# schematics.net
KiCad netlist of a schematic drawn in EAGLE
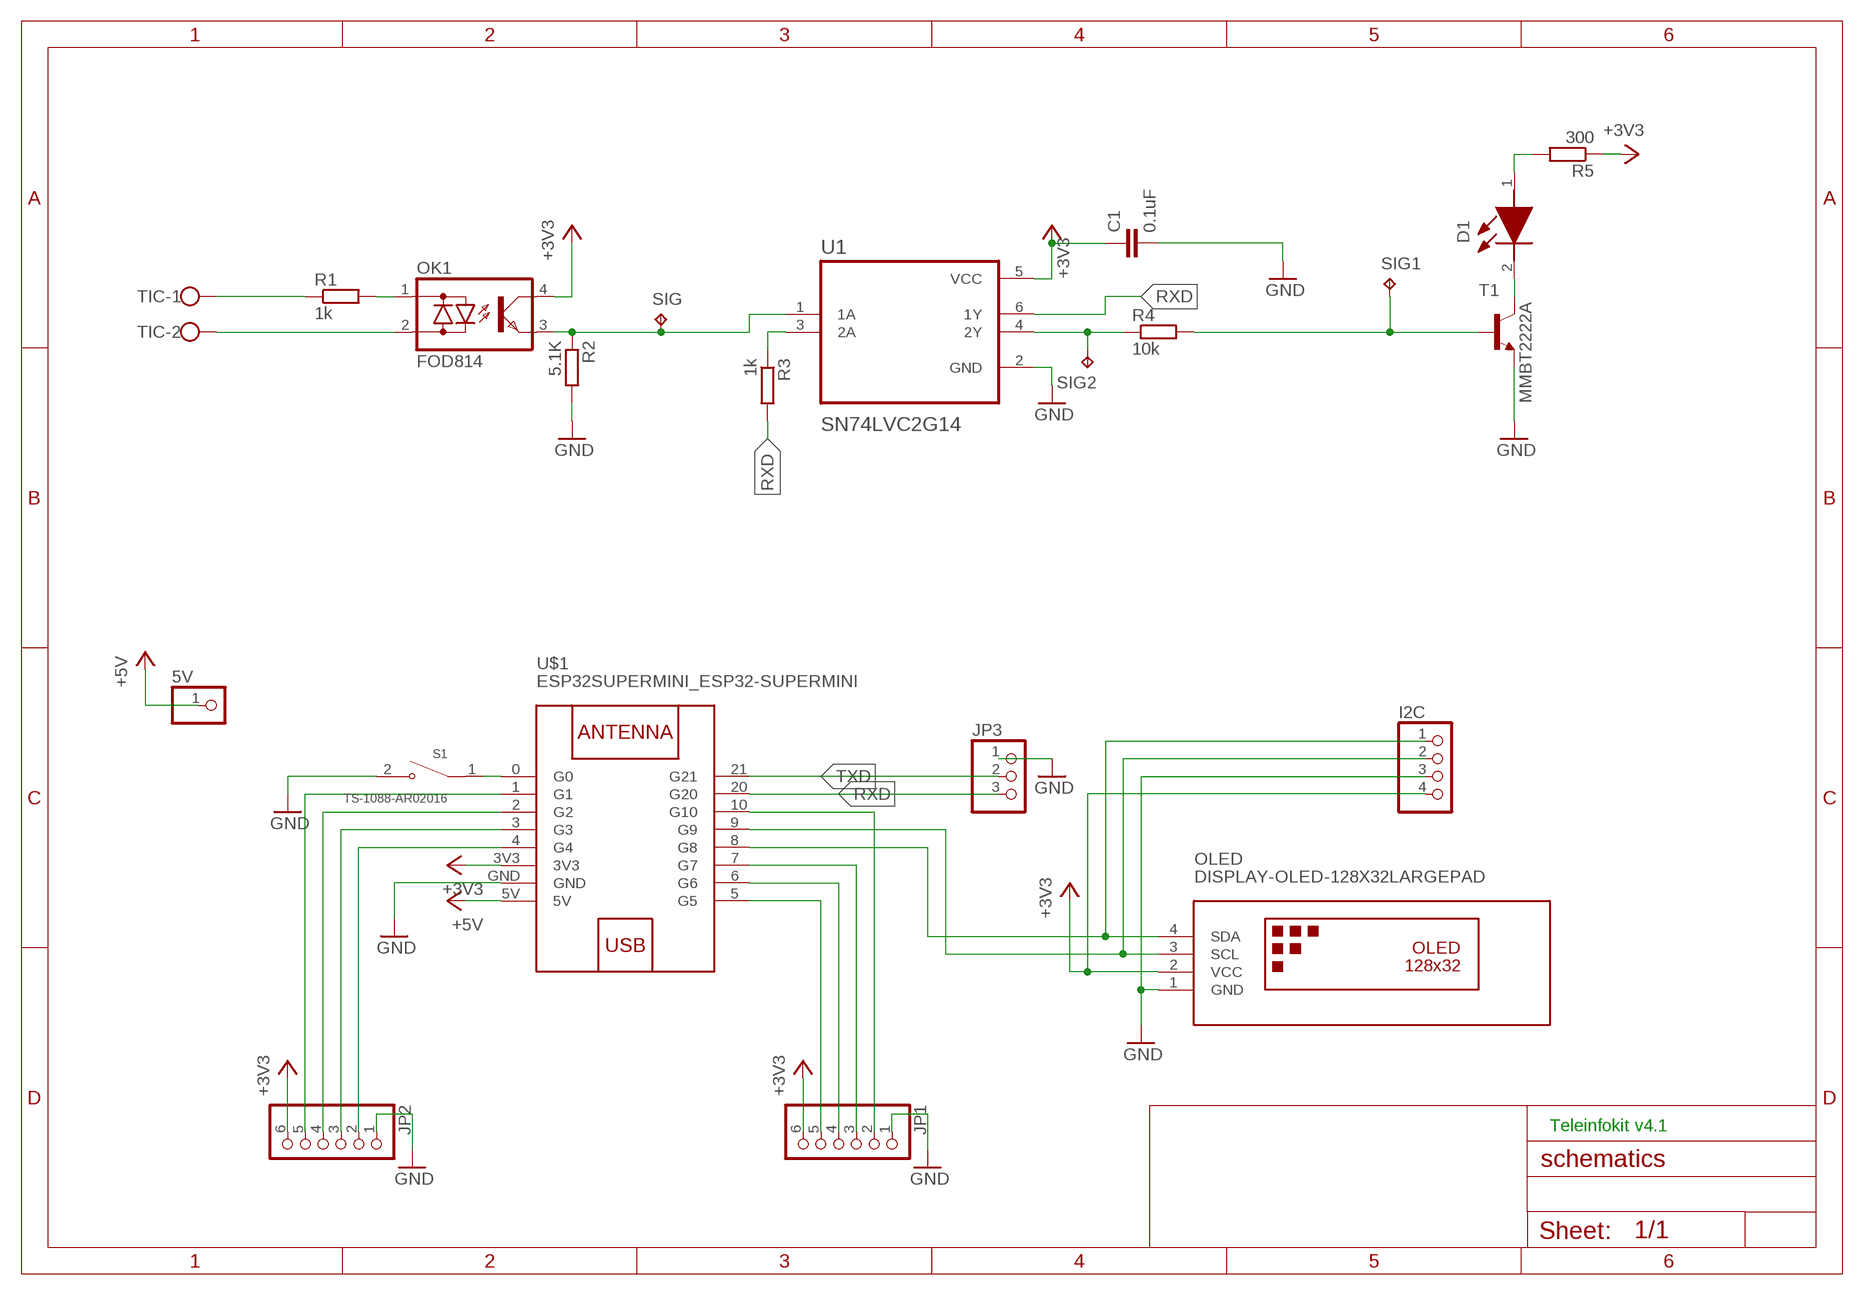
[diagram p0: schematic, sheet 1]

(export (version "E")
  (design (tool "Eeschema 10.0.6"))
  (components
    (comp (ref "5V")
      (value "PINHD-1X1")
      (footprint "eagle-import:1X01")
      (libsource (lib "eagle-import") (part "PINHD-1X1"))
    )
    (comp (ref "C1")
      (value "0.1uF")
      (footprint "eagle-import:C0402K")
      (fields (field (name "LCSC_PART") "C1525"))
      (libsource (lib "eagle-import") (part "C-EUC0402K"))
    )
    (comp (ref "D1")
      (value "17-21SURC_S530-A2_TR8")
      (footprint "eagle-import:1721SURCS530A2TR8")
      (fields (field (name "ARROW_PART_NUMBER") "17-21SURC/S530-A2/TR8"))
      (libsource (lib "eagle-import") (part "17-21SURC_S530-A2_TR8"))
    )
    (comp (ref "I2C")
      (value "PINHD-1X4ROUNDLARGE")
      (footprint "eagle-import:1X04ROUNDLARGE")
      (libsource (lib "eagle-import") (part "PINHD-1X4ROUNDLARGE"))
    )
    (comp (ref "JP1")
      (value "PINHD-1X6CB")
      (footprint "eagle-import:1X06-CLEANBIG")
      (libsource (lib "eagle-import") (part "PINHD-1X6CB"))
    )
    (comp (ref "JP2")
      (value "PINHD-1X6CB")
      (footprint "eagle-import:1X06-CLEANBIG")
      (libsource (lib "eagle-import") (part "PINHD-1X6CB"))
    )
    (comp (ref "JP3")
      (value "PINHD-1X3")
      (footprint "eagle-import:1X03")
      (libsource (lib "eagle-import") (part "PINHD-1X3"))
    )
    (comp (ref "OK1")
      (value "FOD814")
      (footprint "eagle-import:DIL4-SMD")
      (fields
        (field (name "MF") "VISHAY/TELEFUNKEN")
        (field (name "MPN") "SFH6206-3")
        (field (name "LCSC_PART") "C479718")
      )
      (libsource (lib "eagle-import") (part "SFH6206"))
    )
    (comp (ref "OLED")
      (value "DISPLAY-OLED-128X32LARGEPAD")
      (footprint "eagle-import:DISPLAY-OLED-128X32LARGE")
      (fields (field (name "LCSC_PART") "C2718488"))
      (libsource (lib "eagle-import") (part "DISPLAY-OLED-128X32LARGEPAD"))
    )
    (comp (ref "R1")
      (value "1k")
      (footprint "eagle-import:R0805")
      (fields (field (name "LCSC_PART") "C17513"))
      (libsource (lib "eagle-import") (part "R-EU_R0805"))
    )
    (comp (ref "R2")
      (value "5.1K")
      (footprint "eagle-import:R0603")
      (fields (field (name "LCSC_PART") "C23186"))
      (libsource (lib "eagle-import") (part "R-EU_R0603"))
    )
    (comp (ref "R3")
      (value "1k")
      (footprint "eagle-import:R0805")
      (fields (field (name "LCSC_PART") "C17414"))
      (libsource (lib "eagle-import") (part "R-EU_R0805"))
    )
    (comp (ref "R4")
      (value "10k")
      (footprint "eagle-import:R0805")
      (fields (field (name "LCSC_PART") "C17414"))
      (libsource (lib "eagle-import") (part "R-EU_R0805"))
    )
    (comp (ref "R5")
      (value "300")
      (footprint "eagle-import:R0805")
      (fields (field (name "LCSC_PART") "C17617"))
      (libsource (lib "eagle-import") (part "R-EU_R0805"))
    )
    (comp (ref "S1")
      (value "TS-1088-AR02016")
      (footprint "eagle-import:SW_TS-1088-AR02016")
      (fields (field (name "MF") "Xunpu") (field (name "LCSC_PART") "C720477"))
      (libsource (lib "eagle-import") (part "TS-1088-AR02016"))
    )
    (comp (ref "SIG")
      (value "TPB1,27")
      (footprint "eagle-import:B1,27")
      (libsource (lib "eagle-import") (part "TPB1,27"))
    )
    (comp (ref "SIG1")
      (value "TPB1,27")
      (footprint "eagle-import:B1,27")
      (libsource (lib "eagle-import") (part "TPB1,27"))
    )
    (comp (ref "SIG2")
      (value "TPB1,27")
      (footprint "eagle-import:B1,27")
      (libsource (lib "eagle-import") (part "TPB1,27"))
    )
    (comp (ref "T1")
      (value "MMBT2222A")
      (footprint "eagle-import:SOT23-BEC")
      (fields (field (name "LCSC_PART") "C8512"))
      (libsource (lib "eagle-import") (part "-NPN-SOT23-BECMMBT2222ALT1"))
    )
    (comp (ref "TIC")
      (value "W237-102")
      (footprint "eagle-import:W237-102")
      (fields (field (name "MPN") "237-102"))
      (libsource (lib "eagle-import") (part "W237-102"))
    )
    (comp (ref "U$1")
      (value "ESP32SUPERMINI_ESP32-SUPERMINI")
      (footprint "eagle-import:ESP32SUPERMINI_ESP32-SUPERMINI")
      (libsource (lib "eagle-import") (part "ESP32SUPERMINI_ESP32-SUPERMINI"))
    )
    (comp (ref "U1")
      (value "SN74LVC2G14")
      (footprint "eagle-import:SOT95P280X145-6N")
      (fields
        (field (name "MF") "Texas Instruments")
        (field (name "MP") "SN74LVC2G14DBVR")
        (field (name "LCSC_PART") "C12401")
      )
      (libsource (lib "eagle-import") (part "SN74LVC2G14DBVR"))
    )
  )
  (nets
    (net (code "1") (name "+3V3") (class "Default")
      (node (ref "C1") (pin "1") (pinfunction "1_1") (pintype "passive"))
      (node (ref "I2C") (pin "4") (pinfunction "4_4") (pintype "passive"))
      (node (ref "JP1") (pin "6") (pinfunction "6_6") (pintype "passive"))
      (node (ref "JP2") (pin "6") (pinfunction "6_6") (pintype "passive"))
      (node (ref "OK1") (pin "4") (pinfunction "C_4") (pintype "passive"))
      (node (ref "OLED") (pin "2") (pinfunction "VCC_2") (pintype "power_in"))
      (node (ref "R5") (pin "1") (pinfunction "1_1") (pintype "passive"))
      (node (ref "U$1") (pin "3V3") (pinfunction "3V3_3V3") (pintype "power_in"))
      (node (ref "U1") (pin "5") (pinfunction "VCC_5") (pintype "power_in"))
    )
    (net (code "2") (name "+5V") (class "Default")
      (node (ref "5V") (pin "1") (pinfunction "1_1") (pintype "passive"))
      (node (ref "U$1") (pin "5V") (pinfunction "5V_5V") (pintype "power_in"))
    )
    (net (code "3") (name "GND") (class "Default")
      (node (ref "C1") (pin "2") (pinfunction "2_2") (pintype "passive"))
      (node (ref "I2C") (pin "3") (pinfunction "3_3") (pintype "passive"))
      (node (ref "JP1") (pin "1") (pinfunction "1_1") (pintype "passive"))
      (node (ref "JP2") (pin "1") (pinfunction "1_1") (pintype "passive"))
      (node (ref "JP3") (pin "1") (pinfunction "1_1") (pintype "passive"))
      (node (ref "OLED") (pin "1") (pinfunction "GND_1") (pintype "power_in"))
      (node (ref "R2") (pin "2") (pinfunction "2_2") (pintype "passive"))
      (node (ref "S1") (pin "2") (pinfunction "2_2") (pintype "passive"))
      (node (ref "T1") (pin "E") (pinfunction "E_E") (pintype "passive"))
      (node (ref "U$1") (pin "GND") (pinfunction "GND_GND") (pintype "power_in"))
      (node (ref "U1") (pin "2") (pinfunction "GND_2") (pintype "power_in"))
    )
    (net (code "4") (name "Net-(D1-A)") (class "Default")
      (node (ref "D1") (pin "1") (pinfunction "A_1") (pintype "bidirectional"))
      (node (ref "R5") (pin "2") (pinfunction "2_2") (pintype "passive"))
    )
    (net (code "5") (name "Net-(D1-K)") (class "Default")
      (node (ref "D1") (pin "2") (pinfunction "K_2") (pintype "bidirectional"))
      (node (ref "T1") (pin "C") (pinfunction "C_C") (pintype "passive"))
    )
    (net (code "6") (name "Net-(OK1-AC1)") (class "Default")
      (node (ref "OK1") (pin "1") (pinfunction "AC1_1") (pintype "passive"))
      (node (ref "R1") (pin "2") (pinfunction "2_2") (pintype "passive"))
    )
    (net (code "7") (name "Net-(OK1-AC2)") (class "Default")
      (node (ref "OK1") (pin "2") (pinfunction "AC2_2") (pintype "passive"))
      (node (ref "TIC") (pin "2") (pinfunction "KL_2") (pintype "passive"))
    )
    (net (code "8") (name "Net-(OK1-E)") (class "Default")
      (node (ref "OK1") (pin "3") (pinfunction "E_3") (pintype "passive"))
      (node (ref "R2") (pin "1") (pinfunction "1_1") (pintype "passive"))
      (node (ref "SIG") (pin "TP") (pinfunction "TP_TP") (pintype "input"))
      (node (ref "U1") (pin "1") (pinfunction "1A_1") (pintype "input"))
    )
    (net (code "9") (name "Net-(OLED-SCL)") (class "Default")
      (node (ref "I2C") (pin "2") (pinfunction "2_2") (pintype "passive"))
      (node (ref "OLED") (pin "3") (pinfunction "SCL_3") (pintype "bidirectional"))
      (node (ref "U$1") (pin "9") (pinfunction "G9_9") (pintype "bidirectional"))
    )
    (net (code "10") (name "Net-(OLED-SDA)") (class "Default")
      (node (ref "I2C") (pin "1") (pinfunction "1_1") (pintype "passive"))
      (node (ref "OLED") (pin "4") (pinfunction "SDA_4") (pintype "bidirectional"))
      (node (ref "U$1") (pin "8") (pinfunction "G8_8") (pintype "bidirectional"))
    )
    (net (code "11") (name "Net-(R4-Pad2)") (class "Default")
      (node (ref "R4") (pin "2") (pinfunction "2_2") (pintype "passive"))
      (node (ref "SIG1") (pin "TP") (pinfunction "TP_TP") (pintype "input"))
      (node (ref "T1") (pin "B") (pinfunction "B_B") (pintype "passive"))
    )
    (net (code "12") (name "Net-(TICA-KL)") (class "Default")
      (node (ref "R1") (pin "1") (pinfunction "1_1") (pintype "passive"))
      (node (ref "TIC") (pin "1") (pinfunction "KL_1") (pintype "passive"))
    )
    (net (code "13") (name "Net-(U$1-G0)") (class "Default")
      (node (ref "S1") (pin "1") (pinfunction "1_1") (pintype "passive"))
      (node (ref "U$1") (pin "0") (pinfunction "G0_0") (pintype "bidirectional"))
    )
    (net (code "14") (name "Net-(U$1-G1)") (class "Default")
      (node (ref "JP2") (pin "5") (pinfunction "5_5") (pintype "passive"))
      (node (ref "U$1") (pin "1") (pinfunction "G1_1") (pintype "bidirectional"))
    )
    (net (code "15") (name "Net-(U$1-G2)") (class "Default")
      (node (ref "JP2") (pin "4") (pinfunction "4_4") (pintype "passive"))
      (node (ref "U$1") (pin "2") (pinfunction "G2_2") (pintype "bidirectional"))
    )
    (net (code "16") (name "Net-(U$1-G3)") (class "Default")
      (node (ref "JP2") (pin "3") (pinfunction "3_3") (pintype "passive"))
      (node (ref "U$1") (pin "3") (pinfunction "G3_3") (pintype "bidirectional"))
    )
    (net (code "17") (name "Net-(U$1-G4)") (class "Default")
      (node (ref "JP2") (pin "2") (pinfunction "2_2") (pintype "passive"))
      (node (ref "U$1") (pin "4") (pinfunction "G4_4") (pintype "bidirectional"))
    )
    (net (code "18") (name "Net-(U$1-G5)") (class "Default")
      (node (ref "JP1") (pin "5") (pinfunction "5_5") (pintype "passive"))
      (node (ref "U$1") (pin "5") (pinfunction "G5_5") (pintype "bidirectional"))
    )
    (net (code "19") (name "Net-(U$1-G6)") (class "Default")
      (node (ref "JP1") (pin "4") (pinfunction "4_4") (pintype "passive"))
      (node (ref "U$1") (pin "6") (pinfunction "G6_6") (pintype "bidirectional"))
    )
    (net (code "20") (name "Net-(U$1-G7)") (class "Default")
      (node (ref "JP1") (pin "3") (pinfunction "3_3") (pintype "passive"))
      (node (ref "U$1") (pin "7") (pinfunction "G7_7") (pintype "bidirectional"))
    )
    (net (code "21") (name "Net-(U$1-G10)") (class "Default")
      (node (ref "JP1") (pin "2") (pinfunction "2_2") (pintype "passive"))
      (node (ref "U$1") (pin "10") (pinfunction "G10_10") (pintype "bidirectional"))
    )
    (net (code "22") (name "Net-(U1-2A)") (class "Default")
      (node (ref "R3") (pin "1") (pinfunction "1_1") (pintype "passive"))
      (node (ref "U1") (pin "3") (pinfunction "2A_3") (pintype "input"))
    )
    (net (code "23") (name "Net-(U1-2Y)") (class "Default")
      (node (ref "R4") (pin "1") (pinfunction "1_1") (pintype "passive"))
      (node (ref "SIG2") (pin "TP") (pinfunction "TP_TP") (pintype "input"))
      (node (ref "U1") (pin "4") (pinfunction "2Y_4") (pintype "output"))
    )
    (net (code "24") (name "RXD") (class "Default")
      (node (ref "JP3") (pin "3") (pinfunction "3_3") (pintype "passive"))
      (node (ref "R3") (pin "2") (pinfunction "2_2") (pintype "passive"))
      (node (ref "U$1") (pin "20") (pinfunction "G20_20") (pintype "bidirectional"))
      (node (ref "U1") (pin "6") (pinfunction "1Y_6") (pintype "output"))
    )
    (net (code "25") (name "TXD") (class "Default")
      (node (ref "JP3") (pin "2") (pinfunction "2_2") (pintype "passive"))
      (node (ref "U$1") (pin "21") (pinfunction "G21_21") (pintype "bidirectional"))
    )
  )
)
